# Sockets.net
KiCad netlist of a schematic drawn in Altium Designer
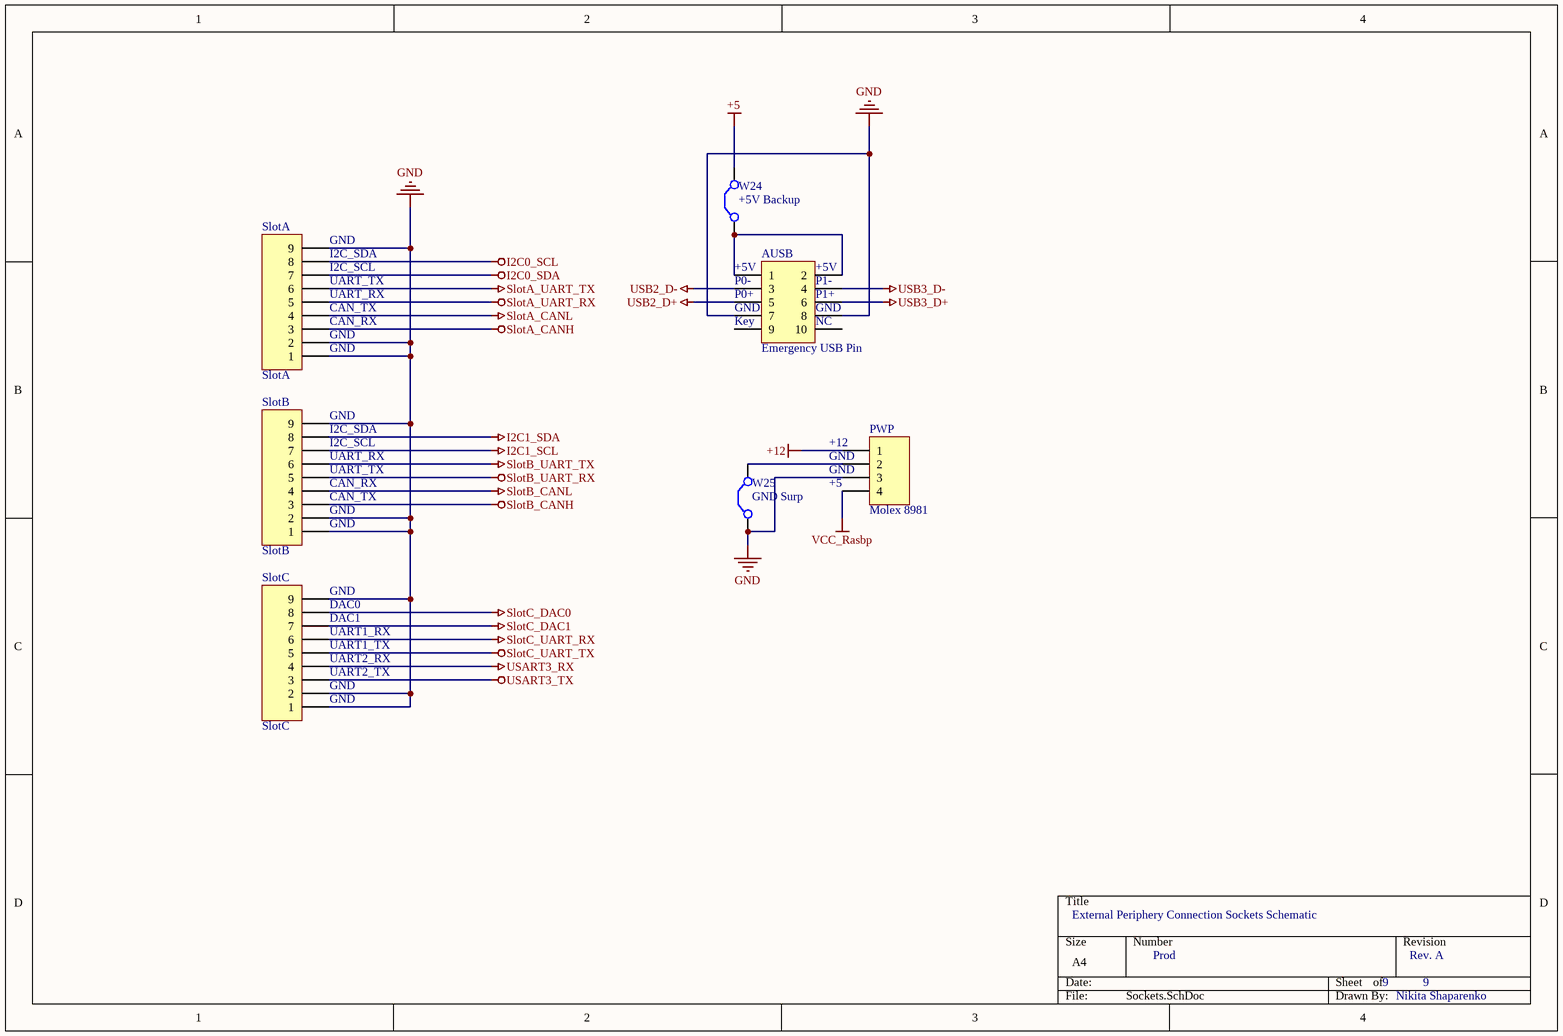
[diagram p0: Sockets.SchDoc]

(export (version "E")
  (design (tool "Eeschema 10.0.6"))
  (components
    (comp (ref "AUSB")
      (value "Emergency USB Pin")
      (footprint "HDR2X5")
      (description "Header, 5-Pin, Dual row")
      (fields (field (name "PUBLISHER") "Altium Limited"))
      (libsource (lib "Miscellaneous Connectors") (part "Header 5X2"))
    )
    (comp (ref "PWP")
      (value "Molex 8981")
      (footprint "HDR1X4")
      (description "Header, 4-Pin")
      (fields (field (name "PUBLISHER") "Altium Limited"))
      (libsource (lib "Miscellaneous Connectors") (part "Header 4"))
    )
    (comp (ref "SlotA")
      (value "SlotA")
      (footprint "SATA Socket")
      (description "Header, 9-Pin")
      (fields (field (name "PUBLISHER") "Altium Limited"))
      (libsource (lib "Miscellaneous Connectors") (part "Header 9"))
    )
    (comp (ref "SlotB")
      (value "SlotB")
      (footprint "SATA Socket")
      (description "Header, 9-Pin")
      (fields (field (name "PUBLISHER") "Altium Limited"))
      (libsource (lib "Miscellaneous Connectors") (part "Header 9"))
    )
    (comp (ref "SlotC")
      (value "SlotC")
      (footprint "SATA Socket")
      (description "Header, 9-Pin")
      (fields (field (name "PUBLISHER") "Altium Limited"))
      (libsource (lib "Miscellaneous Connectors") (part "Header 9"))
    )
    (comp (ref "W24")
      (value "+5V Backup")
      (footprint "RAD-0.1")
      (description "Jumper Wire")
      (fields (field (name "PUBLISHER") "Altium Limited"))
      (libsource (lib "Miscellaneous Devices") (part "Jumper"))
    )
    (comp (ref "W25")
      (value "GND Surp")
      (footprint "RAD-0.1")
      (description "Jumper Wire")
      (fields (field (name "PUBLISHER") "Altium Limited"))
      (libsource (lib "Miscellaneous Devices") (part "Jumper"))
    )
  )
  (nets
    (net (code "1") (name "+5") (class "Default")
      (node (ref "W24") (pin "2") (pinfunction "C2_2") (pintype "passive"))
    )
    (net (code "2") (name "+12") (class "Default")
      (node (ref "PWP") (pin "1") (pinfunction "1_1") (pintype "passive"))
    )
    (net (code "3") (name "GND") (class "Default")
      (node (ref "AUSB") (pin "7") (pinfunction "7_7") (pintype "passive"))
      (node (ref "AUSB") (pin "8") (pinfunction "8_8") (pintype "passive"))
      (node (ref "PWP") (pin "3") (pinfunction "3_3") (pintype "passive"))
      (node (ref "SlotA") (pin "1") (pinfunction "1_1") (pintype "passive"))
      (node (ref "SlotA") (pin "2") (pinfunction "2_2") (pintype "passive"))
      (node (ref "SlotA") (pin "9") (pinfunction "9_9") (pintype "passive"))
      (node (ref "SlotB") (pin "1") (pinfunction "1_1") (pintype "passive"))
      (node (ref "SlotB") (pin "2") (pinfunction "2_2") (pintype "passive"))
      (node (ref "SlotB") (pin "9") (pinfunction "9_9") (pintype "passive"))
      (node (ref "SlotC") (pin "1") (pinfunction "1_1") (pintype "passive"))
      (node (ref "SlotC") (pin "2") (pinfunction "2_2") (pintype "passive"))
      (node (ref "SlotC") (pin "9") (pinfunction "9_9") (pintype "passive"))
      (node (ref "W25") (pin "1") (pinfunction "C1_1") (pintype "passive"))
    )
    (net (code "4") (name "I2C0_SCL") (class "Default")
      (node (ref "SlotA") (pin "8") (pinfunction "8_8") (pintype "passive"))
    )
    (net (code "5") (name "I2C0_SDA") (class "Default")
      (node (ref "SlotA") (pin "7") (pinfunction "7_7") (pintype "passive"))
    )
    (net (code "6") (name "I2C1_SCL") (class "Default")
      (node (ref "SlotB") (pin "7") (pinfunction "7_7") (pintype "passive"))
    )
    (net (code "7") (name "I2C1_SDA") (class "Default")
      (node (ref "SlotB") (pin "8") (pinfunction "8_8") (pintype "passive"))
    )
    (net (code "8") (name "Net-(W24-C1)") (class "Default")
      (node (ref "AUSB") (pin "1") (pinfunction "1_1") (pintype "passive"))
      (node (ref "AUSB") (pin "2") (pinfunction "2_2") (pintype "passive"))
      (node (ref "W24") (pin "1") (pinfunction "C1_1") (pintype "passive"))
    )
    (net (code "9") (name "Net-(W25-C2)") (class "Default")
      (node (ref "PWP") (pin "2") (pinfunction "2_2") (pintype "passive"))
      (node (ref "W25") (pin "2") (pinfunction "C2_2") (pintype "passive"))
    )
    (net (code "10") (name "SlotA_CANH") (class "Default")
      (node (ref "SlotA") (pin "3") (pinfunction "3_3") (pintype "passive"))
    )
    (net (code "11") (name "SlotA_CANL") (class "Default")
      (node (ref "SlotA") (pin "4") (pinfunction "4_4") (pintype "passive"))
    )
    (net (code "12") (name "SlotA_UART_RX") (class "Default")
      (node (ref "SlotA") (pin "5") (pinfunction "5_5") (pintype "passive"))
    )
    (net (code "13") (name "SlotA_UART_TX") (class "Default")
      (node (ref "SlotA") (pin "6") (pinfunction "6_6") (pintype "passive"))
    )
    (net (code "14") (name "SlotB_CANH") (class "Default")
      (node (ref "SlotB") (pin "3") (pinfunction "3_3") (pintype "passive"))
    )
    (net (code "15") (name "SlotB_CANL") (class "Default")
      (node (ref "SlotB") (pin "4") (pinfunction "4_4") (pintype "passive"))
    )
    (net (code "16") (name "SlotB_UART_RX") (class "Default")
      (node (ref "SlotB") (pin "5") (pinfunction "5_5") (pintype "passive"))
    )
    (net (code "17") (name "SlotB_UART_TX") (class "Default")
      (node (ref "SlotB") (pin "6") (pinfunction "6_6") (pintype "passive"))
    )
    (net (code "18") (name "SlotC_DAC0") (class "Default")
      (node (ref "SlotC") (pin "8") (pinfunction "8_8") (pintype "passive"))
    )
    (net (code "19") (name "SlotC_DAC1") (class "Default")
      (node (ref "SlotC") (pin "7") (pinfunction "7_7") (pintype "passive"))
    )
    (net (code "20") (name "SlotC_UART_RX") (class "Default")
      (node (ref "SlotC") (pin "6") (pinfunction "6_6") (pintype "passive"))
    )
    (net (code "21") (name "SlotC_UART_TX") (class "Default")
      (node (ref "SlotC") (pin "5") (pinfunction "5_5") (pintype "passive"))
    )
    (net (code "22") (name "USART3_RX") (class "Default")
      (node (ref "SlotC") (pin "4") (pinfunction "4_4") (pintype "passive"))
    )
    (net (code "23") (name "USART3_TX") (class "Default")
      (node (ref "SlotC") (pin "3") (pinfunction "3_3") (pintype "passive"))
    )
    (net (code "24") (name "USB2_D+") (class "Default")
      (node (ref "AUSB") (pin "5") (pinfunction "5_5") (pintype "passive"))
    )
    (net (code "25") (name "USB2_D-") (class "Default")
      (node (ref "AUSB") (pin "3") (pinfunction "3_3") (pintype "passive"))
    )
    (net (code "26") (name "USB3_D+") (class "Default")
      (node (ref "AUSB") (pin "6") (pinfunction "6_6") (pintype "passive"))
    )
    (net (code "27") (name "USB3_D-") (class "Default")
      (node (ref "AUSB") (pin "4") (pinfunction "4_4") (pintype "passive"))
    )
    (net (code "28") (name "VCC_Rasbp") (class "Default")
      (node (ref "PWP") (pin "4") (pinfunction "4_4") (pintype "passive"))
    )
    (net (code "29") (name "unconnected-(AUSB-Pad9)") (class "Default")
      (node (ref "AUSB") (pin "9") (pinfunction "9_9") (pintype "passive"))
    )
    (net (code "30") (name "unconnected-(AUSB-Pad10)") (class "Default")
      (node (ref "AUSB") (pin "10") (pinfunction "10_10") (pintype "passive"))
    )
  )
)
